# LCD.net
KiCad netlist of a schematic drawn in Altium Designer
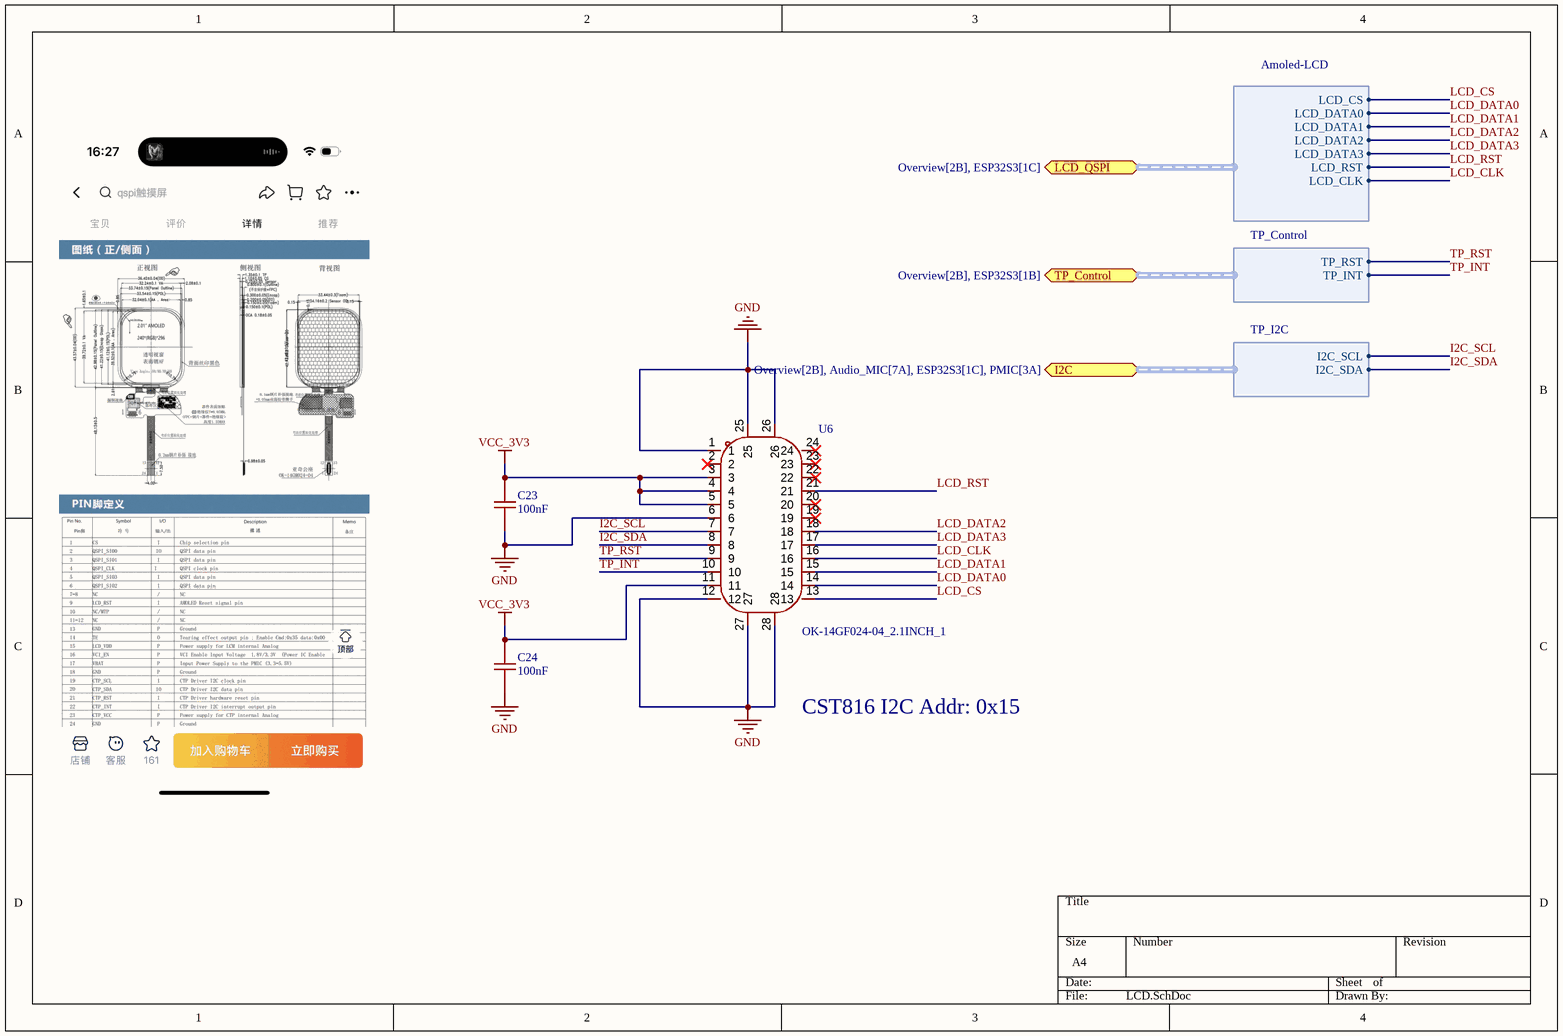
[diagram p0: LCD.SchDoc]

(export (version "E")
  (design (tool "Eeschema 10.0.6"))
  (components
    (comp (ref "C23")
      (value "100nF")
      (footprint "C0402")
      (description "50V 100nF X7R ±10% 0402 Ceramic Capacitors ROHS")
      (libsource (lib "RLC") (part "100nF"))
    )
    (comp (ref "C24")
      (value "100nF")
      (footprint "C0402")
      (description "50V 100nF X7R ±10% 0402 Ceramic Capacitors ROHS")
      (libsource (lib "RLC") (part "100nF"))
    )
    (comp (ref "U6")
      (value "OK-14GF024-04_2.1INCH_1")
      (footprint "CONN-SMD_24P-P0.40_OK-14GF024-04_2.1INCH")
      (description "OK- 14 0.4mm 24Pin")
      (libsource (lib "Connector") (part "OK-14GF024-04_2.1INCH_1"))
    )
  )
  (nets
    (net (code "4") (name "/I2C_SCL") (class "Default")
      (node (ref "U6") (pin "7") (pinfunction "7_7") (pintype "passive"))
    )
    (net (code "5") (name "/I2C_SDA") (class "Default")
      (node (ref "U6") (pin "8") (pinfunction "8_8") (pintype "passive"))
    )
    (net (code "6") (name "/LCD_CLK") (class "Default")
      (node (ref "U6") (pin "16") (pinfunction "16_16") (pintype "passive"))
    )
    (net (code "7") (name "/LCD_CS") (class "Default")
      (node (ref "U6") (pin "13") (pinfunction "13_13") (pintype "passive"))
    )
    (net (code "8") (name "/LCD_DATA0") (class "Default")
      (node (ref "U6") (pin "14") (pinfunction "14_14") (pintype "passive"))
    )
    (net (code "9") (name "/LCD_DATA1") (class "Default")
      (node (ref "U6") (pin "15") (pinfunction "15_15") (pintype "passive"))
    )
    (net (code "10") (name "/LCD_DATA2") (class "Default")
      (node (ref "U6") (pin "18") (pinfunction "18_18") (pintype "passive"))
    )
    (net (code "11") (name "/LCD_DATA3") (class "Default")
      (node (ref "U6") (pin "17") (pinfunction "17_17") (pintype "passive"))
    )
    (net (code "12") (name "/LCD_RST") (class "Default")
      (node (ref "U6") (pin "21") (pinfunction "21_21") (pintype "passive"))
    )
    (net (code "13") (name "/TP_INT") (class "Default")
      (node (ref "U6") (pin "10") (pinfunction "10_10") (pintype "passive"))
    )
    (net (code "14") (name "/TP_RST") (class "Default")
      (node (ref "U6") (pin "9") (pinfunction "9_9") (pintype "passive"))
    )
    (net (code "18") (name "GND") (class "Default")
      (node (ref "C23") (pin "1") (pinfunction "1_1") (pintype "passive"))
      (node (ref "C24") (pin "1") (pinfunction "1_1") (pintype "passive"))
      (node (ref "U6") (pin "1") (pinfunction "1_1") (pintype "passive"))
      (node (ref "U6") (pin "12") (pinfunction "12_12") (pintype "passive"))
      (node (ref "U6") (pin "25") (pinfunction "25_25") (pintype "passive"))
      (node (ref "U6") (pin "26") (pinfunction "26_26") (pintype "passive"))
      (node (ref "U6") (pin "27") (pinfunction "27_27") (pintype "passive"))
      (node (ref "U6") (pin "28") (pinfunction "28_28") (pintype "passive"))
      (node (ref "U6") (pin "6") (pinfunction "6_6") (pintype "passive"))
    )
    (net (code "19") (name "VCC_3V3") (class "Default")
      (node (ref "C23") (pin "2") (pinfunction "2_2") (pintype "passive"))
      (node (ref "C24") (pin "2") (pinfunction "2_2") (pintype "passive"))
      (node (ref "U6") (pin "11") (pinfunction "11_11") (pintype "passive"))
      (node (ref "U6") (pin "3") (pinfunction "3_3") (pintype "passive"))
      (node (ref "U6") (pin "4") (pinfunction "4_4") (pintype "passive"))
      (node (ref "U6") (pin "5") (pinfunction "5_5") (pintype "passive"))
    )
    (net (code "20") (name "unconnected-(U6-Pad2)") (class "Default")
      (node (ref "U6") (pin "2") (pinfunction "2_2") (pintype "passive+no_connect"))
    )
    (net (code "21") (name "unconnected-(U6-Pad19)") (class "Default")
      (node (ref "U6") (pin "19") (pinfunction "19_19") (pintype "passive+no_connect"))
    )
    (net (code "22") (name "unconnected-(U6-Pad20)") (class "Default")
      (node (ref "U6") (pin "20") (pinfunction "20_20") (pintype "passive+no_connect"))
    )
    (net (code "23") (name "unconnected-(U6-Pad22)") (class "Default")
      (node (ref "U6") (pin "22") (pinfunction "22_22") (pintype "passive+no_connect"))
    )
    (net (code "24") (name "unconnected-(U6-Pad23)") (class "Default")
      (node (ref "U6") (pin "23") (pinfunction "23_23") (pintype "passive+no_connect"))
    )
    (net (code "25") (name "unconnected-(U6-Pad24)") (class "Default")
      (node (ref "U6") (pin "24") (pinfunction "24_24") (pintype "passive+no_connect"))
    )
  )
)
